# MCU.net
KiCad netlist of a schematic drawn in Altium Designer
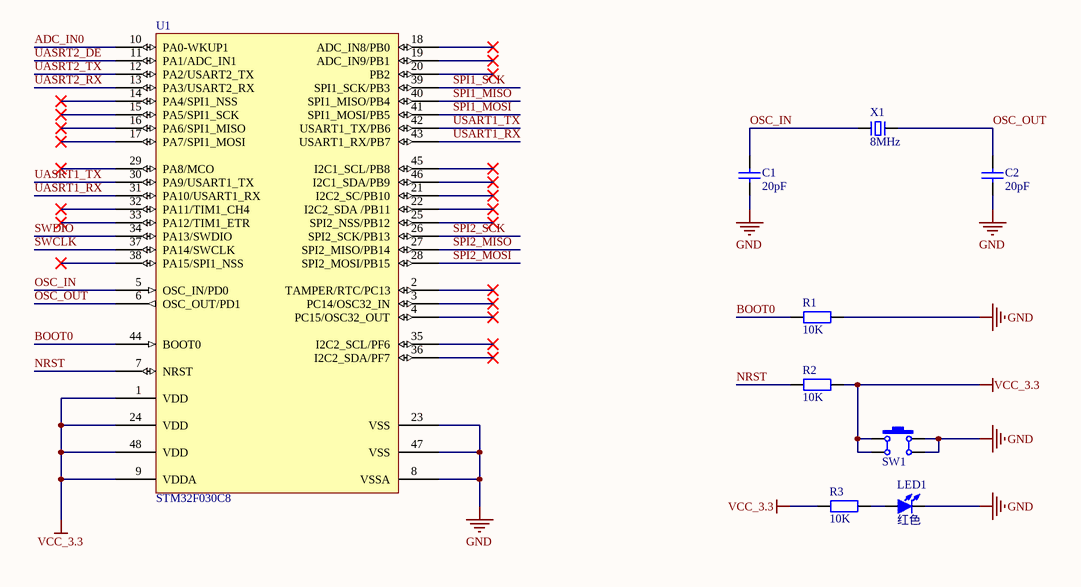
[diagram p0: MCU.SchDoc]

(export (version "E")
  (design (tool "Eeschema 10.0.6"))
  (components
    (comp (ref "C1")
      (value "20pF")
      (footprint "C0402_L")
      (description "贴片电容")
      (fields (field (name "4.作者声明") "旨为整合最全库集,欢迎转载,禁止商用！-冰凌猫") (field (name "1.库作者") "冰凌猫"))
      (libsource (lib "0.1 - 电阻-电容-电感-磁珠-电位器") (part "C"))
    )
    (comp (ref "C2")
      (value "20pF")
      (footprint "C0402_L")
      (description "贴片电容")
      (fields (field (name "4.作者声明") "旨为整合最全库集,欢迎转载,禁止商用！-冰凌猫") (field (name "1.库作者") "冰凌猫"))
      (libsource (lib "0.1 - 电阻-电容-电感-磁珠-电位器") (part "C"))
    )
    (comp (ref "LED1")
      (value "红色")
      (footprint "LED0603_R")
      (description "贴片LED")
      (fields (field (name "1.库作者") "冰凌猫") (field (name "4.作者声明") "旨为整合最全库集,欢迎转载,禁止商用！-冰凌猫"))
      (libsource (lib "0.3 - LED发光二极管") (part "LED-SMD"))
    )
    (comp (ref "R1")
      (value "10K")
      (footprint "R0402_L")
      (description "贴片电阻")
      (fields (field (name "4.作者声明") "旨为整合最全库集,欢迎转载,禁止商用！-冰凌猫") (field (name "1.库作者") "冰凌猫"))
      (libsource (lib "0.1 - 电阻-电容-电感-磁珠-电位器") (part "R"))
    )
    (comp (ref "R2")
      (value "10K")
      (footprint "R0402_L")
      (description "贴片电阻")
      (fields (field (name "4.作者声明") "旨为整合最全库集,欢迎转载,禁止商用！-冰凌猫") (field (name "1.库作者") "冰凌猫"))
      (libsource (lib "0.1 - 电阻-电容-电感-磁珠-电位器") (part "R"))
    )
    (comp (ref "R3")
      (value "10K")
      (footprint "R0402_L")
      (description "贴片电阻")
      (fields (field (name "4.作者声明") "旨为整合最全库集,欢迎转载,禁止商用！-冰凌猫") (field (name "1.库作者") "冰凌猫"))
      (libsource (lib "0.1 - 电阻-电容-电感-磁珠-电位器") (part "R"))
    )
    (comp (ref "SW1")
      (value "4x4x1.5")
      (footprint "SW SMD-4*4*1.5")
      (description "贴片4x4轻触开关")
      (fields (field (name "1.库作者") "冰凌猫") (field (name "4.作者声明") "旨为整合最全库集,欢迎转载,禁止商用！-冰凌猫"))
      (libsource (lib "0.7 - 常用按键-开关-蜂鸣器-电池-测试点") (part "TSW SMD-4x4"))
    )
    (comp (ref "U1")
      (value "STM32F030C8")
      (footprint "LQFP48 7X7_N")
      (description "Flaah:64/RAM:8/IO:39")
      (fields (field (name "1.库作者") "冰凌猫") (field (name "4.作者声明") "旨为整合最全库集,欢迎转载,禁止商用！-冰凌猫"))
      (libsource (lib "2.3 - STM32 F0系列单片机") (part "STM32F030C8"))
    )
    (comp (ref "X1")
      (value "8MHz")
      (footprint "OSC HC-49S")
      (description "2脚无源脚晶振")
      (fields (field (name "1.库作者") "冰凌猫") (field (name "4.作者声明") "旨为整合最全库集,欢迎转载,禁止商用！-冰凌猫"))
      (libsource (lib "0.5 - 保险丝-晶振-光耦") (part "XTAL-2P"))
    )
  )
  (nets
    (net (code "1") (name "/ADC_IN0") (class "Default")
      (node (ref "U1") (pin "10") (pinfunction "PA0-WKUP1_10") (pintype "bidirectional"))
    )
    (net (code "2") (name "/BOOT0") (class "Default")
      (node (ref "R1") (pin "1") (pinfunction "1_1") (pintype "passive"))
      (node (ref "U1") (pin "44") (pinfunction "BOOT0_44") (pintype "input"))
    )
    (net (code "3") (name "/NRST") (class "Default")
      (node (ref "R2") (pin "1") (pinfunction "1_1") (pintype "passive"))
      (node (ref "U1") (pin "7") (pinfunction "NRST_7") (pintype "bidirectional"))
    )
    (net (code "4") (name "/OSC_IN") (class "Default")
      (node (ref "C1") (pin "2") (pinfunction "2_2") (pintype "passive"))
      (node (ref "U1") (pin "5") (pinfunction "OSC_IN/PD0_5") (pintype "input"))
      (node (ref "X1") (pin "1") (pinfunction "1_1") (pintype "passive"))
    )
    (net (code "5") (name "/OSC_OUT") (class "Default")
      (node (ref "C2") (pin "2") (pinfunction "2_2") (pintype "passive"))
      (node (ref "U1") (pin "6") (pinfunction "OSC_OUT/PD1_6") (pintype "output"))
      (node (ref "X1") (pin "2") (pinfunction "2_2") (pintype "passive"))
    )
    (net (code "6") (name "/SPI1_MISO") (class "Default")
      (node (ref "U1") (pin "40") (pinfunction "SPI1_MISO/PB4_40") (pintype "bidirectional"))
    )
    (net (code "7") (name "/SPI1_MOSI") (class "Default")
      (node (ref "U1") (pin "41") (pinfunction "SPI1_MOSI/PB5_41") (pintype "bidirectional"))
    )
    (net (code "8") (name "/SPI1_SCK") (class "Default")
      (node (ref "U1") (pin "39") (pinfunction "SPI1_SCK/PB3_39") (pintype "bidirectional"))
    )
    (net (code "9") (name "/SPI2_MISO") (class "Default")
      (node (ref "U1") (pin "27") (pinfunction "SPI2_MISO/PB14_27") (pintype "bidirectional"))
    )
    (net (code "10") (name "/SPI2_MOSI") (class "Default")
      (node (ref "U1") (pin "28") (pinfunction "SPI2_MOSI/PB15_28") (pintype "bidirectional"))
    )
    (net (code "11") (name "/SPI2_SCK") (class "Default")
      (node (ref "U1") (pin "26") (pinfunction "SPI2_SCK/PB13_26") (pintype "bidirectional"))
    )
    (net (code "12") (name "/SWCLK") (class "Default")
      (node (ref "U1") (pin "37") (pinfunction "PA14/SWCLK_37") (pintype "bidirectional"))
    )
    (net (code "13") (name "/SWDIO") (class "Default")
      (node (ref "U1") (pin "34") (pinfunction "PA13/SWDIO_34") (pintype "bidirectional"))
    )
    (net (code "14") (name "/UASRT1_RX") (class "Default")
      (node (ref "U1") (pin "31") (pinfunction "PA10/USART1_RX_31") (pintype "bidirectional"))
    )
    (net (code "15") (name "/UASRT1_TX") (class "Default")
      (node (ref "U1") (pin "30") (pinfunction "PA9/USART1_TX_30") (pintype "bidirectional"))
    )
    (net (code "16") (name "/UASRT2_DE") (class "Default")
      (node (ref "U1") (pin "11") (pinfunction "PA1/ADC_IN1_11") (pintype "bidirectional"))
    )
    (net (code "17") (name "/UASRT2_RX") (class "Default")
      (node (ref "U1") (pin "13") (pinfunction "PA3/USART2_RX_13") (pintype "bidirectional"))
    )
    (net (code "18") (name "/UASRT2_TX") (class "Default")
      (node (ref "U1") (pin "12") (pinfunction "PA2/USART2_TX_12") (pintype "bidirectional"))
    )
    (net (code "19") (name "/USART1_RX") (class "Default")
      (node (ref "U1") (pin "43") (pinfunction "USART1_RX/PB7_43") (pintype "bidirectional"))
    )
    (net (code "20") (name "/USART1_TX") (class "Default")
      (node (ref "U1") (pin "42") (pinfunction "USART1_TX/PB6_42") (pintype "bidirectional"))
    )
    (net (code "21") (name "GND") (class "Default")
      (node (ref "C1") (pin "1") (pinfunction "1_1") (pintype "passive"))
      (node (ref "C2") (pin "1") (pinfunction "1_1") (pintype "passive"))
      (node (ref "LED1") (pin "2") (pinfunction "K_2") (pintype "passive"))
      (node (ref "R1") (pin "2") (pinfunction "2_2") (pintype "passive"))
      (node (ref "SW1") (pin "2") (pinfunction "2_2") (pintype "passive"))
      (node (ref "SW1") (pin "3") (pinfunction "3_3") (pintype "passive"))
      (node (ref "U1") (pin "23") (pinfunction "VSS_23") (pintype "power_in"))
      (node (ref "U1") (pin "47") (pinfunction "VSS_47") (pintype "power_in"))
      (node (ref "U1") (pin "8") (pinfunction "VSSA_8") (pintype "power_in"))
    )
    (net (code "22") (name "Net-(LED1-A)") (class "Default")
      (node (ref "LED1") (pin "1") (pinfunction "A_1") (pintype "passive"))
      (node (ref "R3") (pin "2") (pinfunction "2_2") (pintype "passive"))
    )
    (net (code "23") (name "VCC_3.3") (class "Default")
      (node (ref "R2") (pin "2") (pinfunction "2_2") (pintype "passive"))
      (node (ref "R3") (pin "1") (pinfunction "1_1") (pintype "passive"))
      (node (ref "SW1") (pin "1") (pinfunction "1_1") (pintype "passive"))
      (node (ref "SW1") (pin "4") (pinfunction "4_4") (pintype "passive"))
      (node (ref "U1") (pin "1") (pinfunction "VDD_1") (pintype "power_in"))
      (node (ref "U1") (pin "24") (pinfunction "VDD_24") (pintype "power_in"))
      (node (ref "U1") (pin "48") (pinfunction "VDD_48") (pintype "power_in"))
      (node (ref "U1") (pin "9") (pinfunction "VDDA_9") (pintype "power_in"))
    )
    (net (code "24") (name "unconnected-(U1-ADC_IN8{slash}PB0-Pad18)") (class "Default")
      (node (ref "U1") (pin "18") (pinfunction "ADC_IN8/PB0_18") (pintype "bidirectional+no_connect"))
    )
    (net (code "25") (name "unconnected-(U1-ADC_IN9{slash}PB1-Pad19)") (class "Default")
      (node (ref "U1") (pin "19") (pinfunction "ADC_IN9/PB1_19") (pintype "bidirectional+no_connect"))
    )
    (net (code "26") (name "unconnected-(U1-I2C1_SCL{slash}PB8-Pad45)") (class "Default")
      (node (ref "U1") (pin "45") (pinfunction "I2C1_SCL/PB8_45") (pintype "bidirectional+no_connect"))
    )
    (net (code "27") (name "unconnected-(U1-I2C1_SDA{slash}PB9-Pad46)") (class "Default")
      (node (ref "U1") (pin "46") (pinfunction "I2C1_SDA/PB9_46") (pintype "bidirectional+no_connect"))
    )
    (net (code "28") (name "unconnected-(U1-I2C2_SCL{slash}PF6-Pad35)") (class "Default")
      (node (ref "U1") (pin "35") (pinfunction "I2C2_SCL/PF6_35") (pintype "bidirectional+no_connect"))
    )
    (net (code "29") (name "unconnected-(U1-I2C2_SC{slash}PB10-Pad21)") (class "Default")
      (node (ref "U1") (pin "21") (pinfunction "I2C2_SC/PB10_21") (pintype "bidirectional+no_connect"))
    )
    (net (code "30") (name "unconnected-(U1-I2C2_SDA_{slash}PB11-Pad22)") (class "Default")
      (node (ref "U1") (pin "22") (pinfunction "I2C2_SDA_/PB11_22") (pintype "bidirectional+no_connect"))
    )
    (net (code "31") (name "unconnected-(U1-I2C2_SDA{slash}PF7-Pad36)") (class "Default")
      (node (ref "U1") (pin "36") (pinfunction "I2C2_SDA/PF7_36") (pintype "bidirectional+no_connect"))
    )
    (net (code "32") (name "unconnected-(U1-PA4{slash}SPI1_NSS-Pad14)") (class "Default")
      (node (ref "U1") (pin "14") (pinfunction "PA4/SPI1_NSS_14") (pintype "bidirectional+no_connect"))
    )
    (net (code "33") (name "unconnected-(U1-PA5{slash}SPI1_SCK-Pad15)") (class "Default")
      (node (ref "U1") (pin "15") (pinfunction "PA5/SPI1_SCK_15") (pintype "bidirectional+no_connect"))
    )
    (net (code "34") (name "unconnected-(U1-PA6{slash}SPI1_MISO-Pad16)") (class "Default")
      (node (ref "U1") (pin "16") (pinfunction "PA6/SPI1_MISO_16") (pintype "bidirectional+no_connect"))
    )
    (net (code "35") (name "unconnected-(U1-PA7{slash}SPI1_MOSI-Pad17)") (class "Default")
      (node (ref "U1") (pin "17") (pinfunction "PA7/SPI1_MOSI_17") (pintype "bidirectional+no_connect"))
    )
    (net (code "36") (name "unconnected-(U1-PA8{slash}MCO-Pad29)") (class "Default")
      (node (ref "U1") (pin "29") (pinfunction "PA8/MCO_29") (pintype "bidirectional+no_connect"))
    )
    (net (code "37") (name "unconnected-(U1-PA11{slash}TIM1_CH4-Pad32)") (class "Default")
      (node (ref "U1") (pin "32") (pinfunction "PA11/TIM1_CH4_32") (pintype "bidirectional+no_connect"))
    )
    (net (code "38") (name "unconnected-(U1-PA12{slash}TIM1_ETR-Pad33)") (class "Default")
      (node (ref "U1") (pin "33") (pinfunction "PA12/TIM1_ETR_33") (pintype "bidirectional+no_connect"))
    )
    (net (code "39") (name "unconnected-(U1-PA15{slash}SPI1_NSS-Pad38)") (class "Default")
      (node (ref "U1") (pin "38") (pinfunction "PA15/SPI1_NSS_38") (pintype "bidirectional+no_connect"))
    )
    (net (code "40") (name "unconnected-(U1-PB2-Pad20)") (class "Default")
      (node (ref "U1") (pin "20") (pinfunction "PB2_20") (pintype "bidirectional+no_connect"))
    )
    (net (code "41") (name "unconnected-(U1-PC14{slash}OSC32_IN-Pad3)") (class "Default")
      (node (ref "U1") (pin "3") (pinfunction "PC14/OSC32_IN_3") (pintype "bidirectional+no_connect"))
    )
    (net (code "42") (name "unconnected-(U1-PC15{slash}OSC32_OUT-Pad4)") (class "Default")
      (node (ref "U1") (pin "4") (pinfunction "PC15/OSC32_OUT_4") (pintype "bidirectional+no_connect"))
    )
    (net (code "43") (name "unconnected-(U1-SPI2_NSS{slash}PB12-Pad25)") (class "Default")
      (node (ref "U1") (pin "25") (pinfunction "SPI2_NSS/PB12_25") (pintype "bidirectional+no_connect"))
    )
    (net (code "44") (name "unconnected-(U1-TAMPER{slash}RTC{slash}PC13-Pad2)") (class "Default")
      (node (ref "U1") (pin "2") (pinfunction "TAMPER/RTC/PC13_2") (pintype "bidirectional+no_connect"))
    )
  )
)
